# sensors.net
KiCad netlist of a schematic drawn in EAGLE
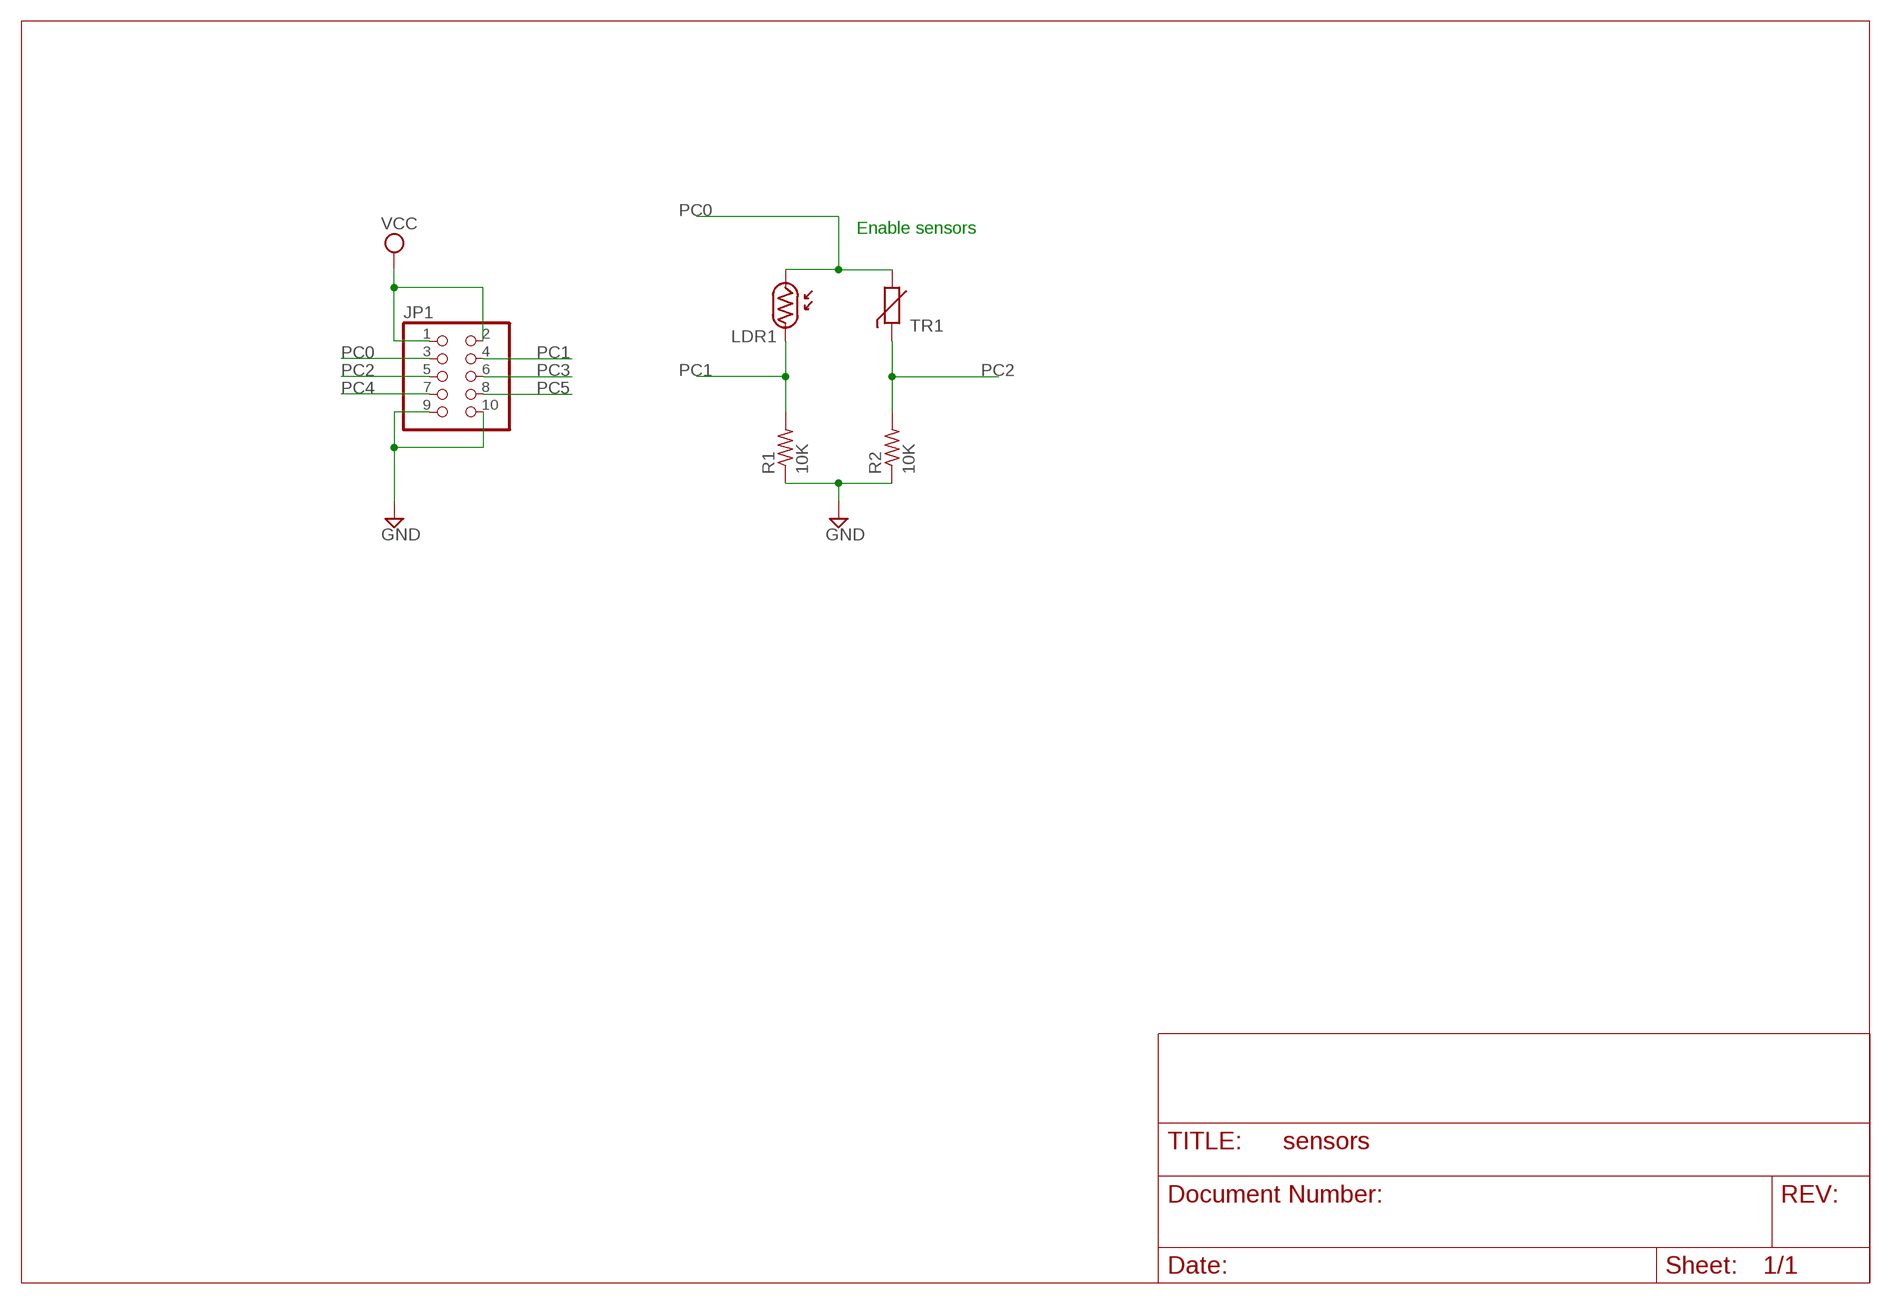
[diagram p0: schematic, sheet 1]

(export (version "E")
  (design (tool "Eeschema 10.0.6"))
  (components
    (comp (ref "JP1")
      (value "PINHD-2X5")
      (footprint "eagle-import:2X05")
      (libsource (lib "eagle-import") (part "PINHD-2X5"))
    )
    (comp (ref "LDR1")
      (value "LDR")
      (footprint "eagle-import:3MM")
      (libsource (lib "eagle-import") (part "LDR"))
    )
    (comp (ref "R1")
      (value "10K")
      (footprint "eagle-import:0204_5")
      (libsource (lib "eagle-import") (part "R-US_0204/5"))
    )
    (comp (ref "R2")
      (value "10K")
      (footprint "eagle-import:0204_5")
      (libsource (lib "eagle-import") (part "R-US_0204/5"))
    )
    (comp (ref "TR1")
      (value "THERMISTOR_R-5")
      (footprint "eagle-import:R-5")
      (libsource (lib "eagle-import") (part "THERMISTOR_R-5"))
    )
  )
  (nets
    (net (code "1") (name "/PC0") (class "Default")
      (node (ref "JP1") (pin "3") (pinfunction "3_3") (pintype "passive"))
      (node (ref "LDR1") (pin "P$1") (pinfunction "P$1_P$1") (pintype "passive"))
      (node (ref "TR1") (pin "2") (pinfunction "2_2") (pintype "passive"))
    )
    (net (code "2") (name "/PC1") (class "Default")
      (node (ref "JP1") (pin "4") (pinfunction "4_4") (pintype "passive"))
      (node (ref "LDR1") (pin "P$2") (pinfunction "P$2_P$2") (pintype "passive"))
      (node (ref "R1") (pin "2") (pinfunction "2_2") (pintype "passive"))
    )
    (net (code "3") (name "/PC2") (class "Default")
      (node (ref "JP1") (pin "5") (pinfunction "5_5") (pintype "passive"))
      (node (ref "R2") (pin "2") (pinfunction "2_2") (pintype "passive"))
      (node (ref "TR1") (pin "1") (pinfunction "1_1") (pintype "passive"))
    )
    (net (code "4") (name "/PC3") (class "Default")
      (node (ref "JP1") (pin "6") (pinfunction "6_6") (pintype "passive"))
    )
    (net (code "5") (name "/PC4") (class "Default")
      (node (ref "JP1") (pin "7") (pinfunction "7_7") (pintype "passive"))
    )
    (net (code "6") (name "/PC5") (class "Default")
      (node (ref "JP1") (pin "8") (pinfunction "8_8") (pintype "passive"))
    )
    (net (code "7") (name "GND") (class "Default")
      (node (ref "JP1") (pin "10") (pinfunction "10_10") (pintype "passive"))
      (node (ref "JP1") (pin "9") (pinfunction "9_9") (pintype "passive"))
      (node (ref "R1") (pin "1") (pinfunction "1_1") (pintype "passive"))
      (node (ref "R2") (pin "1") (pinfunction "1_1") (pintype "passive"))
    )
    (net (code "8") (name "VCC") (class "Default")
      (node (ref "JP1") (pin "1") (pinfunction "1_1") (pintype "passive"))
      (node (ref "JP1") (pin "2") (pinfunction "2_2") (pintype "passive"))
    )
  )
)
